# BMS-S06-V01-IsolatedCAN.net
KiCad netlist of a schematic drawn in Altium Designer
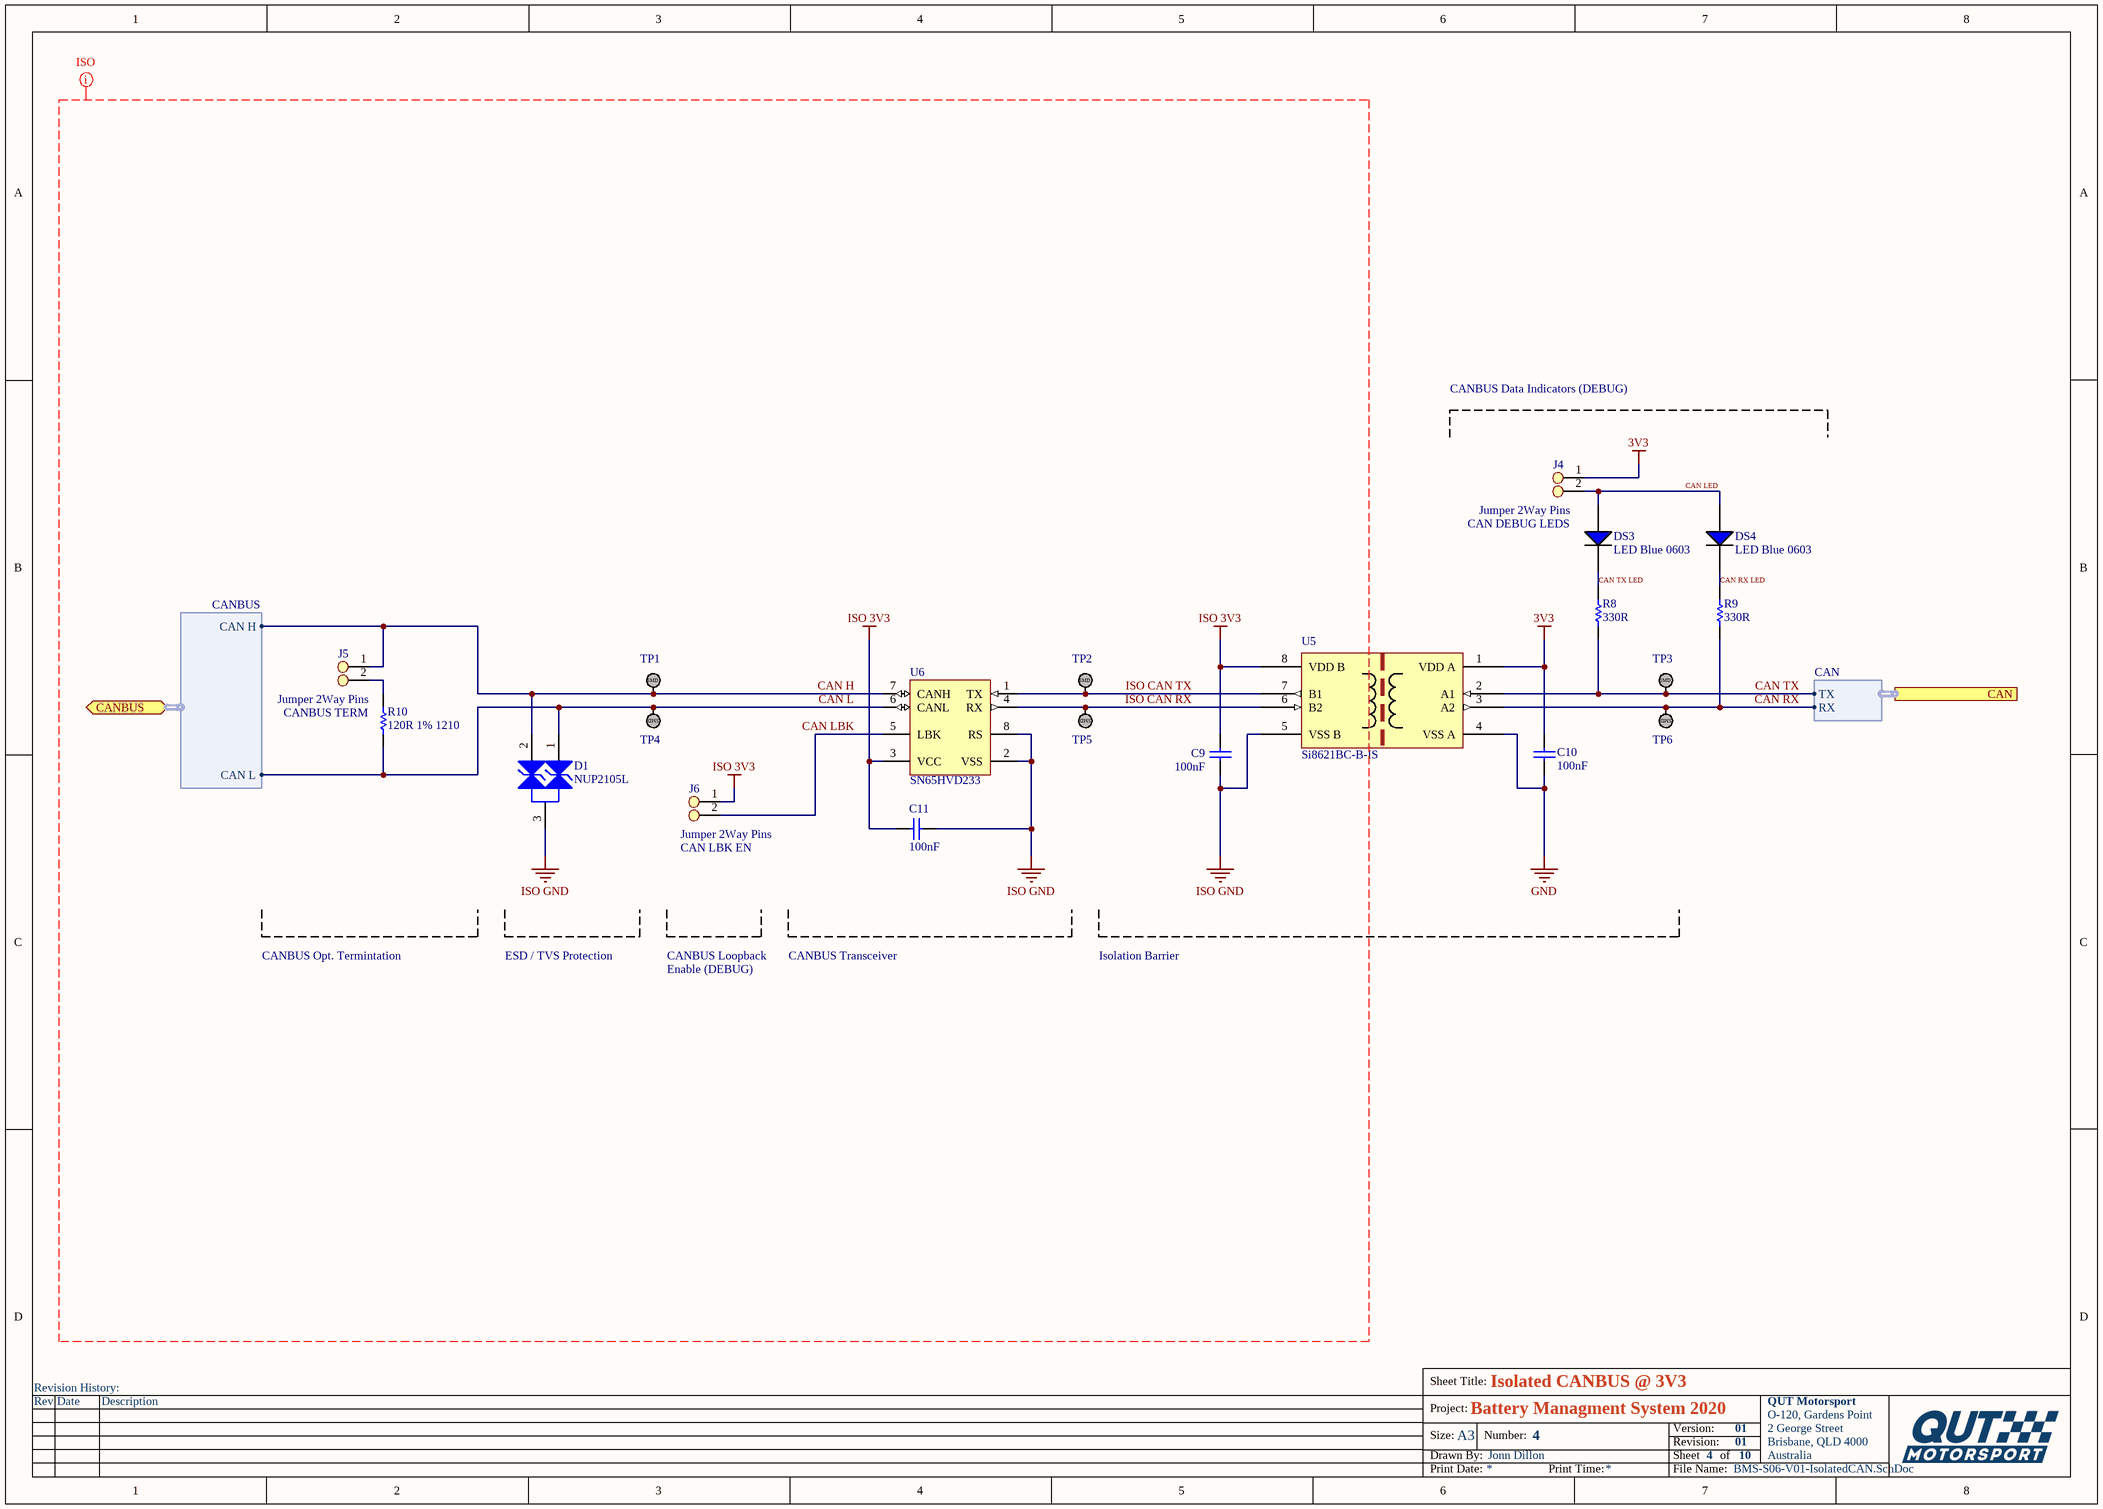
[diagram p0: BMS-S06-V01-IsolatedCAN.SchDoc]

(export (version "E")
  (design (tool "Eeschema 10.0.6"))
  (components
    (comp (ref "C9")
      (value "100nF")
      (footprint "Cap_Ceramic_0603")
      (description "Capacitor, Ceramic, SMD, 100nF, 50V, 5%, X7R, 0603")
      (libsource (lib "StandardCapacitors") (part "100nF 50V 5% X7R 0603"))
    )
    (comp (ref "C10")
      (value "100nF")
      (footprint "Cap_Ceramic_0603")
      (description "Capacitor, Ceramic, SMD, 100nF, 50V, 5%, X7R, 0603")
      (libsource (lib "StandardCapacitors") (part "100nF 50V 5% X7R 0603"))
    )
    (comp (ref "C11")
      (value "100nF")
      (footprint "Cap_Ceramic_0603")
      (description "Capacitor, Ceramic, SMD, 100nF, 50V, 5%, X7R, 0603")
      (libsource (lib "StandardCapacitors") (part "100nF 50V 5% X7R 0603"))
    )
    (comp (ref "D1")
      (value "NUP2105L")
      (footprint "NUP2105L")
      (libsource (lib "QUTMS_CANLibrary") (part "NUP2105L"))
    )
    (comp (ref "DS3")
      (value "LED Blue 0603")
      (footprint "LED BLUE 0603")
      (libsource (lib "QUTMS_LEDLibrary") (part "LED BLUE 0603"))
    )
    (comp (ref "DS4")
      (value "LED Blue 0603")
      (footprint "LED BLUE 0603")
      (libsource (lib "QUTMS_LEDLibrary") (part "LED BLUE 0603"))
    )
    (comp (ref "J4")
      (value "Jumper 2Way Pins")
      (footprint "Jumper_2Way_Pin")
      (description "Jumper 2Way Side Pins")
      (libsource (lib "QUTMS_JumperLibrary") (part "Jumper 2Way Side Pins"))
    )
    (comp (ref "J5")
      (value "Jumper 2Way Pins")
      (footprint "Jumper_2Way_Pin")
      (description "Jumper 2Way Side Pins")
      (libsource (lib "QUTMS_JumperLibrary") (part "Jumper 2Way Side Pins"))
    )
    (comp (ref "J6")
      (value "Jumper 2Way Pins")
      (footprint "Jumper_2Way_Pin")
      (description "Jumper 2Way Side Pins")
      (libsource (lib "QUTMS_JumperLibrary") (part "Jumper 2Way Side Pins"))
    )
    (comp (ref "R8")
      (value "330R")
      (footprint "Res_ThinFilm_0603")
      (description "Resistor, SMD, 330R, 0.1W, 5%, 0603")
      (libsource (lib "StandardResistors") (part "330R 5% 0603"))
    )
    (comp (ref "R9")
      (value "330R")
      (footprint "Res_ThinFilm_0603")
      (description "Resistor, SMD, 330R, 0.1W, 5%, 0603")
      (libsource (lib "StandardResistors") (part "330R 5% 0603"))
    )
    (comp (ref "R10")
      (value "120R 1% 1210")
      (footprint "Res_ThinFilm_1210")
      (description "Resistor, SMD, 120R, 0.25W, 1%, 1210")
      (libsource (lib "StandardResistors") (part "120R 1% 1210"))
    )
    (comp (ref "TP1")
      (value "TestPoint_SMD")
      (footprint "TestPointSMD")
      (libsource (lib "StandardTest") (part "TestPoint_SMD"))
    )
    (comp (ref "TP2")
      (value "TestPoint_SMD")
      (footprint "TestPointSMD")
      (libsource (lib "StandardTest") (part "TestPoint_SMD"))
    )
    (comp (ref "TP3")
      (value "TestPoint_SMD")
      (footprint "TestPointSMD")
      (libsource (lib "StandardTest") (part "TestPoint_SMD"))
    )
    (comp (ref "TP4")
      (value "TestPoint_SMD")
      (footprint "TestPointSMD")
      (libsource (lib "StandardTest") (part "TestPoint_SMD"))
    )
    (comp (ref "TP5")
      (value "TestPoint_SMD")
      (footprint "TestPointSMD")
      (libsource (lib "StandardTest") (part "TestPoint_SMD"))
    )
    (comp (ref "TP6")
      (value "TestPoint_SMD")
      (footprint "TestPointSMD")
      (libsource (lib "StandardTest") (part "TestPoint_SMD"))
    )
    (comp (ref "U5")
      (value "Si8621BC-B-IS")
      (footprint "Si8621BC-B-IS")
      (libsource (lib "QUTMS_IsolatorLibrary") (part "Si8621BC-B-IS"))
    )
    (comp (ref "U6")
      (value "SN65HVD233")
      (footprint "SN65HVD233DR")
      (libsource (lib "QUTMS_CANLibrary") (part "SN65HVD233"))
    )
  )
  (nets
    (net (code "3") (name "/CAN H") (class "Default")
      (node (ref "D1") (pin "2") (pinfunction "2_2") (pintype "passive"))
      (node (ref "J5") (pin "1") (pinfunction "1_1") (pintype "passive"))
      (node (ref "TP1") (pin "1") (pinfunction "1_1") (pintype "passive"))
      (node (ref "U6") (pin "7") (pinfunction "CANH_7") (pintype "bidirectional"))
    )
    (net (code "4") (name "/CAN L") (class "Default")
      (node (ref "D1") (pin "1") (pinfunction "1_1") (pintype "passive"))
      (node (ref "R10") (pin "1") (pinfunction "1_1") (pintype "passive"))
      (node (ref "TP4") (pin "1") (pinfunction "1_1") (pintype "passive"))
      (node (ref "U6") (pin "6") (pinfunction "CANL_6") (pintype "bidirectional"))
    )
    (net (code "5") (name "/CAN LBK") (class "Default")
      (node (ref "J6") (pin "2") (pinfunction "2_2") (pintype "passive"))
      (node (ref "U6") (pin "5") (pinfunction "LBK_5") (pintype "passive"))
    )
    (net (code "6") (name "/CAN LED") (class "Default")
      (node (ref "DS3") (pin "1") (pinfunction "A_1") (pintype "passive"))
      (node (ref "DS4") (pin "1") (pinfunction "A_1") (pintype "passive"))
      (node (ref "J4") (pin "2") (pinfunction "2_2") (pintype "passive"))
    )
    (net (code "7") (name "/CAN RX") (class "Default")
      (node (ref "R9") (pin "1") (pinfunction "1_1") (pintype "passive"))
      (node (ref "TP6") (pin "1") (pinfunction "1_1") (pintype "passive"))
      (node (ref "U5") (pin "3") (pinfunction "A2_3") (pintype "output"))
    )
    (net (code "8") (name "/CAN RX LED") (class "Default")
      (node (ref "DS4") (pin "2") (pinfunction "C_2") (pintype "passive"))
      (node (ref "R9") (pin "2") (pinfunction "2_2") (pintype "passive"))
    )
    (net (code "9") (name "/CAN TX") (class "Default")
      (node (ref "R8") (pin "1") (pinfunction "1_1") (pintype "passive"))
      (node (ref "TP3") (pin "1") (pinfunction "1_1") (pintype "passive"))
      (node (ref "U5") (pin "2") (pinfunction "A1_2") (pintype "input"))
    )
    (net (code "10") (name "/CAN TX LED") (class "Default")
      (node (ref "DS3") (pin "2") (pinfunction "C_2") (pintype "passive"))
      (node (ref "R8") (pin "2") (pinfunction "2_2") (pintype "passive"))
    )
    (net (code "11") (name "/ISO CAN RX") (class "Default")
      (node (ref "TP5") (pin "1") (pinfunction "1_1") (pintype "passive"))
      (node (ref "U5") (pin "6") (pinfunction "B2_6") (pintype "input"))
      (node (ref "U6") (pin "4") (pinfunction "RX_4") (pintype "output"))
    )
    (net (code "12") (name "/ISO CAN TX") (class "Default")
      (node (ref "TP2") (pin "1") (pinfunction "1_1") (pintype "passive"))
      (node (ref "U5") (pin "7") (pinfunction "B1_7") (pintype "output"))
      (node (ref "U6") (pin "1") (pinfunction "TX_1") (pintype "input"))
    )
    (net (code "15") (name "3V3") (class "Default")
      (node (ref "C10") (pin "2") (pinfunction "2_2") (pintype "passive"))
      (node (ref "J4") (pin "1") (pinfunction "1_1") (pintype "passive"))
      (node (ref "U5") (pin "1") (pinfunction "VDD_A_1") (pintype "passive"))
    )
    (net (code "16") (name "GND") (class "Default")
      (node (ref "C10") (pin "1") (pinfunction "1_1") (pintype "passive"))
      (node (ref "U5") (pin "4") (pinfunction "VSS_A_4") (pintype "passive"))
    )
    (net (code "17") (name "ISO 3V3") (class "Default")
      (node (ref "C11") (pin "2") (pinfunction "2_2") (pintype "passive"))
      (node (ref "C9") (pin "2") (pinfunction "2_2") (pintype "passive"))
      (node (ref "J6") (pin "1") (pinfunction "1_1") (pintype "passive"))
      (node (ref "U5") (pin "8") (pinfunction "VDD_B_8") (pintype "passive"))
      (node (ref "U6") (pin "3") (pinfunction "VCC_3") (pintype "passive"))
    )
    (net (code "18") (name "ISO GND") (class "Default")
      (node (ref "C11") (pin "1") (pinfunction "1_1") (pintype "passive"))
      (node (ref "C9") (pin "1") (pinfunction "1_1") (pintype "passive"))
      (node (ref "D1") (pin "3") (pinfunction "3_3") (pintype "passive"))
      (node (ref "U5") (pin "5") (pinfunction "VSS_B_5") (pintype "passive"))
      (node (ref "U6") (pin "2") (pinfunction "VSS_2") (pintype "passive"))
      (node (ref "U6") (pin "8") (pinfunction "RS_8") (pintype "passive"))
    )
    (net (code "19") (name "Net-(J5-Pad2)") (class "Default")
      (node (ref "J5") (pin "2") (pinfunction "2_2") (pintype "passive"))
      (node (ref "R10") (pin "2") (pinfunction "2_2") (pintype "passive"))
    )
  )
)
